# 07-POWER.net
KiCad netlist of a schematic drawn in Altium Designer
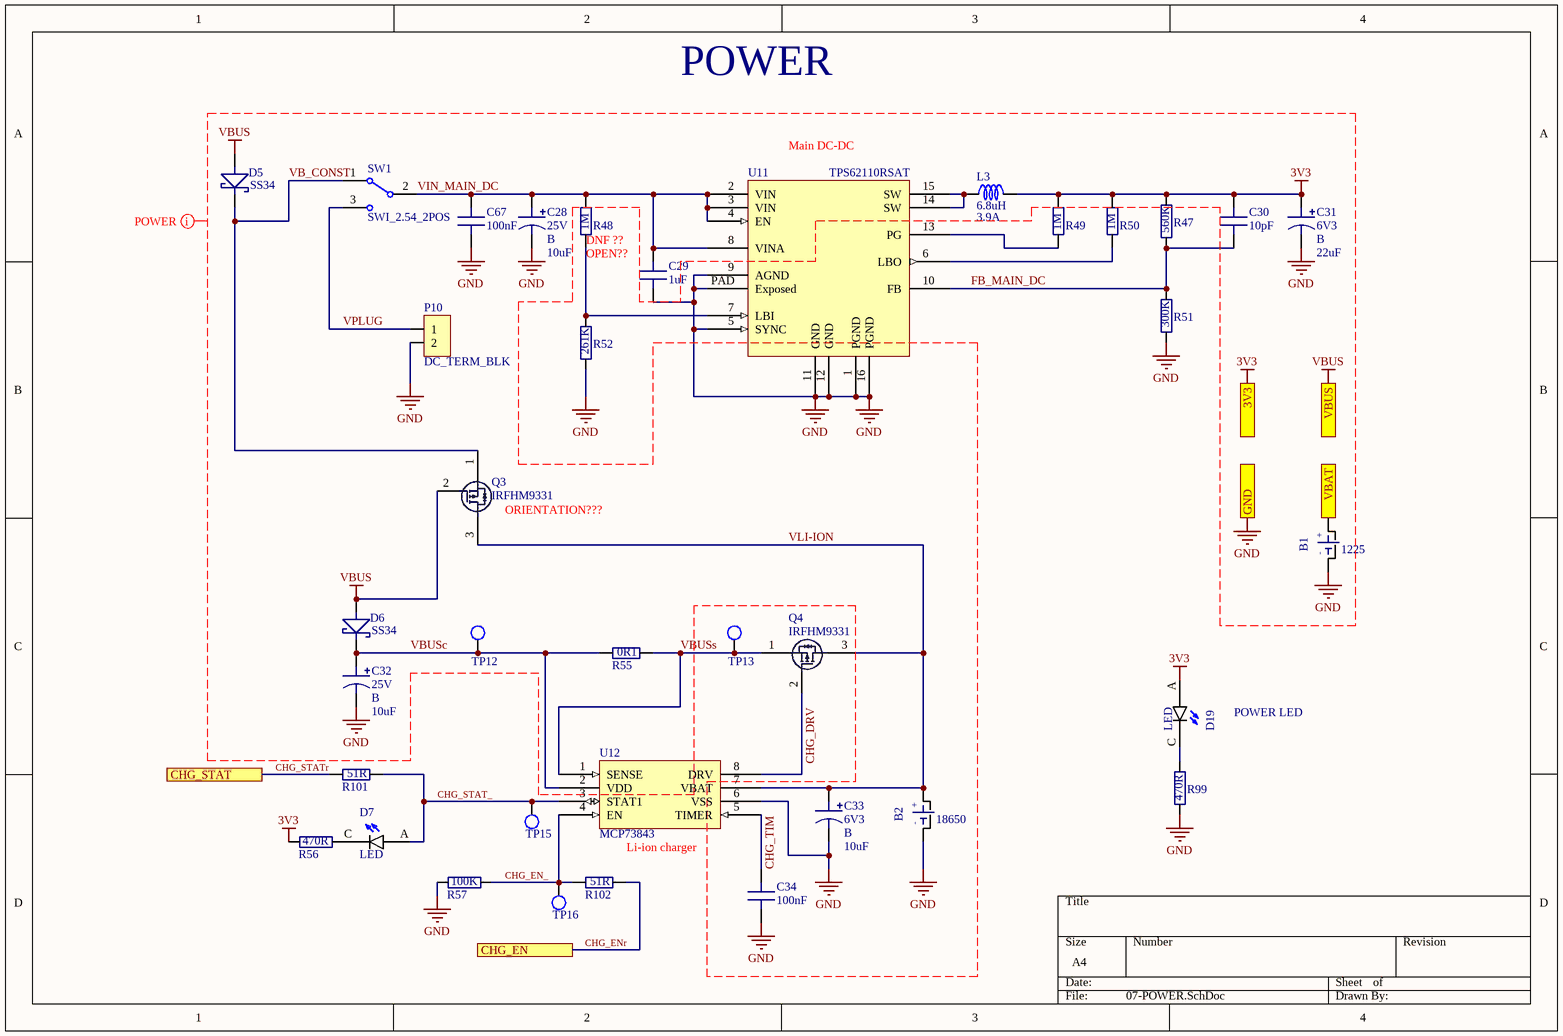
[diagram p0: 07-POWER.SchDoc]

(export (version "E")
  (design (tool "Eeschema 10.0.6"))
  (components
    (comp (ref "B1")
      (value "CR12XX_BH500")
      (footprint "BH500-CR1216/20/25-COMB")
      (description "Coin Cell Battery 3V 12 X 2.5 mm 48mA Holder")
      (fields
        (field (name "MP") "BR1225")
        (field (name "MF") "Panasonic Battery")
        (field (name "SIZE") "1225")
      )
      (libsource (lib "A.Shelestov_Batteries") (part "CR12XX_BH500"))
    )
    (comp (ref "B2")
      (value "18650_KEYS1042_HOLDER")
      (footprint "18650-COMBI")
      (description "18650 Li-ion Battery Holder")
      (fields (field (name "SIZE") "18650"))
      (libsource (lib "A.Shelestov_Batteries") (part "18650_KEYS1042_HOLDER"))
    )
    (comp (ref "C28")
      (value "10uF")
      (footprint "CAP_SIZE_B")
      (description "Tantalum capacitor")
      (fields (field (name "VOLTAGE") "25V") (field (name "SIZE") "B"))
      (libsource (lib "A.Shelestov_Capacitors") (part "CAP_B_10uF_25V"))
    )
    (comp (ref "C29")
      (value "1uF")
      (footprint "C0805")
      (description "Ceramic capacitor")
      (fields (field (name "VOLTAGE") "25V"))
      (libsource (lib "A.Shelestov_Capacitors") (part "C0805_1uF_25V"))
    )
    (comp (ref "C30")
      (value "10pF")
      (footprint "C0603")
      (description "Ceramic capacitor")
      (fields (field (name "VOLTAGE") "25V"))
      (libsource (lib "A.Shelestov_Capacitors") (part "C0603_10pF_25V"))
    )
    (comp (ref "C31")
      (value "22uF")
      (footprint "CAP_SIZE_B")
      (description "Tantalum capacitor")
      (fields (field (name "VOLTAGE") "6V3") (field (name "SIZE") "B"))
      (libsource (lib "A.Shelestov_Capacitors") (part "CAP_B_22uF_6V3"))
    )
    (comp (ref "C32")
      (value "10uF")
      (footprint "CAP_SIZE_B")
      (description "Tantalum capacitor")
      (fields (field (name "VOLTAGE") "25V") (field (name "SIZE") "B"))
      (libsource (lib "A.Shelestov_Capacitors") (part "CAP_B_10uF_25V"))
    )
    (comp (ref "C33")
      (value "10uF")
      (footprint "CAP_SIZE_B")
      (description "Tantalum capacitor")
      (fields (field (name "VOLTAGE") "6V3") (field (name "SIZE") "B"))
      (libsource (lib "A.Shelestov_Capacitors") (part "CAP_B_10uF_6V3"))
    )
    (comp (ref "C34")
      (value "100nF")
      (footprint "C0805")
      (description "Ceramic capacitor")
      (fields (field (name "VOLTAGE") "25V"))
      (libsource (lib "A.Shelestov_Capacitors") (part "C0805_100nF_25V"))
    )
    (comp (ref "C67")
      (value "100nF")
      (footprint "C0805")
      (description "Ceramic capacitor")
      (fields (field (name "VOLTAGE") "25V"))
      (libsource (lib "A.Shelestov_Capacitors") (part "C0805_100nF_25V"))
    )
    (comp (ref "D5")
      (value "SMD-DIODE-SCHOTTKY-40V-3A(DO-214AB)")
      (footprint "DO-214AC")
      (description "Rectifier, Schottky; DO-214AB; 3.0A IF; 0.75V; 40V; 100A IFRM; 10000V/us; 1000pF")
      (fields (field (name "MF") "Vishay") (field (name "MP") "SS34-E3/57T") (field (name "NAME") "SS34"))
      (libsource (lib "ComponentsLib") (part "D_SS-34"))
    )
    (comp (ref "D6")
      (value "SMD-DIODE-SCHOTTKY-40V-3A(DO-214AB)")
      (footprint "DO-214AC")
      (description "Rectifier, Schottky; DO-214AB; 3.0A IF; 0.75V; 40V; 100A IFRM; 10000V/us; 1000pF")
      (fields (field (name "MF") "Vishay") (field (name "MP") "SS34-E3/57T") (field (name "NAME") "SS34"))
      (libsource (lib "ComponentsLib") (part "D_SS-34"))
    )
    (comp (ref "D7")
      (value "LED")
      (footprint "LED_0604")
      (description "Led General")
      (fields (field (name "MF") "Dialight") (field (name "MP") "598-8140-107F"))
      (libsource (lib "ComponentsLib") (part "LED"))
    )
    (comp (ref "D19")
      (value "LED")
      (footprint "LED_0604")
      (description "Led General")
      (fields (field (name "MF") "Dialight") (field (name "MP") "598-8140-107F"))
      (libsource (lib "ComponentsLib") (part "LED"))
    )
    (comp (ref "L3")
      (value "*")
      (footprint "L_CDRH8D43")
      (description "Inductor Generic")
      (fields (field (name "CURRENT") "3.9A") (field (name "INDUCTIVITY") "6.8uH"))
      (libsource (lib "A.Shelestov_Inductors") (part "L_CDHR8D43_6.8uH_3.9A"))
    )
    (comp (ref "P10")
      (value "DC_TERM_BLK")
      (footprint "TERM_BLK_2.54")
      (libsource (lib "ComponentsLib") (part "DC_TERM_BLK"))
    )
    (comp (ref "Q3")
      (value "IRFHM9331")
      (footprint "PQFN-3x3")
      (libsource (lib "ComponentsLib") (part "IRFHM9331"))
    )
    (comp (ref "Q4")
      (value "IRFHM9331")
      (footprint "PQFN-3x3")
      (libsource (lib "ComponentsLib") (part "IRFHM9331"))
    )
    (comp (ref "R47")
      (value "~")
      (footprint "R0805")
      (description "Resistor General")
      (fields (field (name "TOLERANCE") "1%") (field (name "RESISTANCE") "560K"))
      (libsource (lib "A.Shelestov_Resistors") (part "R0805_560K_1%"))
    )
    (comp (ref "R48")
      (value "~")
      (footprint "R0805")
      (description "Resistor General")
      (fields (field (name "TOLERANCE") "1%") (field (name "RESISTANCE") "1M"))
      (libsource (lib "A.Shelestov_Resistors") (part "R0805_1M_1%"))
    )
    (comp (ref "R49")
      (value "~")
      (footprint "R0805")
      (description "Resistor General")
      (fields (field (name "TOLERANCE") "1%") (field (name "RESISTANCE") "1M"))
      (libsource (lib "A.Shelestov_Resistors") (part "R0805_1M_1%"))
    )
    (comp (ref "R50")
      (value "~")
      (footprint "R0805")
      (description "Resistor General")
      (fields (field (name "TOLERANCE") "1%") (field (name "RESISTANCE") "1M"))
      (libsource (lib "A.Shelestov_Resistors") (part "R0805_1M_1%"))
    )
    (comp (ref "R51")
      (value "~")
      (footprint "R0805")
      (description "Resistor General")
      (fields (field (name "TOLERANCE") "1%") (field (name "RESISTANCE") "300K"))
      (libsource (lib "A.Shelestov_Resistors") (part "R0805_300K_1%"))
    )
    (comp (ref "R52")
      (value "~")
      (footprint "R0805")
      (description "Resistor General")
      (fields (field (name "TOLERANCE") "1%") (field (name "RESISTANCE") "261K"))
      (libsource (lib "A.Shelestov_Resistors") (part "R0805_261K_1%"))
    )
    (comp (ref "R55")
      (value "~")
      (footprint "R2512")
      (description "Resistor General")
      (fields (field (name "RESISTANCE") "0R1"))
      (libsource (lib "A.Shelestov_Resistors") (part "R2512_0R1_1%"))
    )
    (comp (ref "R56")
      (value "~")
      (footprint "R0603")
      (description "Resistor General")
      (fields (field (name "TOLERANCE") "5%") (field (name "RESISTANCE") "470R"))
      (libsource (lib "A.Shelestov_Resistors") (part "R0603_470R"))
    )
    (comp (ref "R57")
      (value "~")
      (footprint "R0603")
      (description "Resistor General")
      (fields (field (name "TOLERANCE") "5%") (field (name "RESISTANCE") "100K"))
      (libsource (lib "A.Shelestov_Resistors") (part "R0603_100K"))
    )
    (comp (ref "R99")
      (value "~")
      (footprint "R0603")
      (description "Resistor General")
      (fields (field (name "TOLERANCE") "5%") (field (name "RESISTANCE") "470R"))
      (libsource (lib "A.Shelestov_Resistors") (part "R0603_470R"))
    )
    (comp (ref "R101")
      (value "~")
      (footprint "R0402")
      (description "Resistor General")
      (fields (field (name "RESISTANCE") "51R"))
      (libsource (lib "A.Shelestov_Resistors") (part "R0402_51R"))
    )
    (comp (ref "R102")
      (value "~")
      (footprint "R0402")
      (description "Resistor General")
      (fields (field (name "RESISTANCE") "51R"))
      (libsource (lib "A.Shelestov_Resistors") (part "R0402_51R"))
    )
    (comp (ref "SW1")
      (value "SWI_2.54_2POS")
      (footprint "SW_1x3 2.54")
      (description "Generich 2 pos switch")
      (libsource (lib "ComponentsLib") (part "SWI_2.54_2POS"))
    )
    (comp (ref "TP12")
      (value "TEST_POINT")
      (footprint "TP_1mm")
      (libsource (lib "ComponentsLib") (part "TEST_POINT"))
    )
    (comp (ref "TP13")
      (value "TEST_POINT")
      (footprint "TP_1mm")
      (libsource (lib "ComponentsLib") (part "TEST_POINT"))
    )
    (comp (ref "TP15")
      (value "TEST_POINT")
      (footprint "TP_1mm")
      (libsource (lib "ComponentsLib") (part "TEST_POINT"))
    )
    (comp (ref "TP16")
      (value "TEST_POINT")
      (footprint "TP_1mm")
      (libsource (lib "ComponentsLib") (part "TEST_POINT"))
    )
    (comp (ref "U11")
      (value "TPS62110RSAT")
      (footprint "VQFN-16")
      (description "TPS6211x 17-V, 1.5-A, Synchronous Step-Down Converter")
      (libsource (lib "ComponentsLib") (part "TPS62110RSAT"))
    )
    (comp (ref "U12")
      (value "MCP73843")
      (footprint "MSOP-8-SOP65P490X110-8N")
      (description "MCP73843 Single Li-ion cell charger IC")
      (fields (field (name "MF") "Microchip"))
      (libsource (lib "ComponentsLib") (part "MCP73843"))
    )
  )
  (nets
    (net (code "1") (name "/CHG_DRV") (class "Default")
      (node (ref "Q4") (pin "2") (pinfunction "G_2") (pintype "passive"))
      (node (ref "U12") (pin "8") (pinfunction "DRV_8") (pintype "power_in"))
    )
    (net (code "2") (name "/CHG_EN_") (class "Default")
      (node (ref "R102") (pin "1") (pinfunction "1_1") (pintype "passive"))
      (node (ref "R57") (pin "2") (pinfunction "2_2") (pintype "passive"))
      (node (ref "TP16") (pin "1") (pinfunction "1_1") (pintype "passive"))
      (node (ref "U12") (pin "4") (pinfunction "EN_4") (pintype "input"))
    )
    (net (code "3") (name "/CHG_ENr") (class "Default")
      (node (ref "R102") (pin "2") (pinfunction "2_2") (pintype "passive"))
    )
    (net (code "4") (name "/CHG_STAT_") (class "Default")
      (node (ref "D7") (pin "A") (pinfunction "A_A") (pintype "passive"))
      (node (ref "R101") (pin "2") (pinfunction "2_2") (pintype "passive"))
      (node (ref "TP15") (pin "1") (pinfunction "1_1") (pintype "passive"))
      (node (ref "U12") (pin "3") (pinfunction "STAT1_3") (pintype "bidirectional"))
    )
    (net (code "5") (name "/CHG_STATr") (class "Default")
      (node (ref "R101") (pin "1") (pinfunction "1_1") (pintype "passive"))
    )
    (net (code "6") (name "/CHG_TIM") (class "Default")
      (node (ref "C34") (pin "2") (pinfunction "2_2") (pintype "passive"))
      (node (ref "U12") (pin "5") (pinfunction "TIMER_5") (pintype "input"))
    )
    (net (code "7") (name "/FB_MAIN_DC") (class "Default")
      (node (ref "C30") (pin "2") (pinfunction "2_2") (pintype "passive"))
      (node (ref "R47") (pin "1") (pinfunction "1_1") (pintype "passive"))
      (node (ref "R51") (pin "2") (pinfunction "2_2") (pintype "passive"))
      (node (ref "U11") (pin "10") (pinfunction "FB_10") (pintype "power_in"))
    )
    (net (code "8") (name "/VBAT") (class "Default")
      (node (ref "B1") (pin "POS") (pinfunction "POS_POS") (pintype "passive"))
    )
    (net (code "9") (name "/VBUSc") (class "Default")
      (node (ref "C32") (pin "1") (pinfunction "1_1") (pintype "passive"))
      (node (ref "D6") (pin "C") (pinfunction "NEG_C") (pintype "passive"))
      (node (ref "R55") (pin "1") (pinfunction "1_1") (pintype "passive"))
      (node (ref "TP12") (pin "1") (pinfunction "1_1") (pintype "passive"))
      (node (ref "U12") (pin "2") (pinfunction "VDD_2") (pintype "power_in"))
    )
    (net (code "10") (name "/VBUSs") (class "Default")
      (node (ref "Q4") (pin "1") (pinfunction "S_1") (pintype "passive"))
      (node (ref "R55") (pin "2") (pinfunction "2_2") (pintype "passive"))
      (node (ref "TP13") (pin "1") (pinfunction "1_1") (pintype "passive"))
      (node (ref "U12") (pin "1") (pinfunction "SENSE_1") (pintype "input"))
    )
    (net (code "11") (name "/VB_CONST") (class "Default")
      (node (ref "D5") (pin "C") (pinfunction "NEG_C") (pintype "passive"))
      (node (ref "Q3") (pin "1") (pinfunction "S_1") (pintype "passive"))
      (node (ref "SW1") (pin "1") (pinfunction "1_1") (pintype "passive"))
    )
    (net (code "12") (name "/VIN_MAIN_DC") (class "Default")
      (node (ref "C28") (pin "1") (pinfunction "1_1") (pintype "passive"))
      (node (ref "C29") (pin "2") (pinfunction "2_2") (pintype "passive"))
      (node (ref "C67") (pin "2") (pinfunction "2_2") (pintype "passive"))
      (node (ref "R48") (pin "2") (pinfunction "2_2") (pintype "passive"))
      (node (ref "SW1") (pin "2") (pinfunction "2_2") (pintype "passive"))
      (node (ref "U11") (pin "2") (pinfunction "VIN_2") (pintype "power_in"))
      (node (ref "U11") (pin "3") (pinfunction "VIN_3") (pintype "power_in"))
      (node (ref "U11") (pin "4") (pinfunction "EN_4") (pintype "input"))
      (node (ref "U11") (pin "8") (pinfunction "VINA_8") (pintype "power_in"))
    )
    (net (code "13") (name "/VLI-ION") (class "Default")
      (node (ref "B2") (pin "POS") (pinfunction "POS_POS") (pintype "passive"))
      (node (ref "C33") (pin "1") (pinfunction "1_1") (pintype "passive"))
      (node (ref "Q3") (pin "3") (pinfunction "D_3") (pintype "passive"))
      (node (ref "Q4") (pin "3") (pinfunction "D_3") (pintype "passive"))
      (node (ref "U12") (pin "7") (pinfunction "VBAT_7") (pintype "power_in"))
    )
    (net (code "14") (name "/VPLUG") (class "Default")
      (node (ref "P10") (pin "1") (pinfunction "1_1") (pintype "passive"))
      (node (ref "SW1") (pin "3") (pinfunction "3_3") (pintype "passive"))
    )
    (net (code "15") (name "3V3") (class "Default")
      (node (ref "C30") (pin "1") (pinfunction "1_1") (pintype "passive"))
      (node (ref "C31") (pin "1") (pinfunction "1_1") (pintype "passive"))
      (node (ref "D19") (pin "A") (pinfunction "A_A") (pintype "passive"))
      (node (ref "L3") (pin "2") (pinfunction "2_2") (pintype "passive"))
      (node (ref "R47") (pin "2") (pinfunction "2_2") (pintype "passive"))
      (node (ref "R49") (pin "2") (pinfunction "2_2") (pintype "passive"))
      (node (ref "R50") (pin "2") (pinfunction "2_2") (pintype "passive"))
      (node (ref "R56") (pin "1") (pinfunction "1_1") (pintype "passive"))
    )
    (net (code "16") (name "GND") (class "Default")
      (node (ref "B1") (pin "NEG") (pinfunction "NEG_NEG") (pintype "passive"))
      (node (ref "B2") (pin "NEG") (pinfunction "NEG_NEG") (pintype "passive"))
      (node (ref "C28") (pin "2") (pinfunction "2_2") (pintype "passive"))
      (node (ref "C29") (pin "1") (pinfunction "1_1") (pintype "passive"))
      (node (ref "C31") (pin "2") (pinfunction "2_2") (pintype "passive"))
      (node (ref "C32") (pin "2") (pinfunction "2_2") (pintype "passive"))
      (node (ref "C33") (pin "2") (pinfunction "2_2") (pintype "passive"))
      (node (ref "C34") (pin "1") (pinfunction "1_1") (pintype "passive"))
      (node (ref "C67") (pin "1") (pinfunction "1_1") (pintype "passive"))
      (node (ref "P10") (pin "2") (pinfunction "2_2") (pintype "passive"))
      (node (ref "R51") (pin "1") (pinfunction "1_1") (pintype "passive"))
      (node (ref "R52") (pin "1") (pinfunction "1_1") (pintype "passive"))
      (node (ref "R57") (pin "1") (pinfunction "1_1") (pintype "passive"))
      (node (ref "R99") (pin "1") (pinfunction "1_1") (pintype "passive"))
      (node (ref "U11") (pin "1") (pinfunction "PGND_1") (pintype "power_in"))
      (node (ref "U11") (pin "11") (pinfunction "GND_11") (pintype "power_in"))
      (node (ref "U11") (pin "12") (pinfunction "GND_12") (pintype "power_in"))
      (node (ref "U11") (pin "16") (pinfunction "PGND_16") (pintype "power_in"))
      (node (ref "U11") (pin "5") (pinfunction "SYNC_5") (pintype "input"))
      (node (ref "U11") (pin "9") (pinfunction "AGND_9") (pintype "power_in"))
      (node (ref "U11") (pin "PAD") (pinfunction "Exposed_PAD") (pintype "power_in"))
      (node (ref "U12") (pin "6") (pinfunction "VSS_6") (pintype "power_in"))
    )
    (net (code "17") (name "Net-(D7-PadC)") (class "Default")
      (node (ref "D7") (pin "C") (pinfunction "C_C") (pintype "passive"))
      (node (ref "R56") (pin "2") (pinfunction "2_2") (pintype "passive"))
    )
    (net (code "18") (name "Net-(D19-PadC)") (class "Default")
      (node (ref "D19") (pin "C") (pinfunction "C_C") (pintype "passive"))
      (node (ref "R99") (pin "2") (pinfunction "2_2") (pintype "passive"))
    )
    (net (code "19") (name "Net-(L3-Pad1)") (class "Default")
      (node (ref "L3") (pin "1") (pinfunction "1_1") (pintype "passive"))
      (node (ref "U11") (pin "14") (pinfunction "SW_14") (pintype "power_in"))
      (node (ref "U11") (pin "15") (pinfunction "SW_15") (pintype "power_in"))
    )
    (net (code "20") (name "Net-(U11-LBI)") (class "Default")
      (node (ref "R48") (pin "1") (pinfunction "1_1") (pintype "passive"))
      (node (ref "R52") (pin "2") (pinfunction "2_2") (pintype "passive"))
      (node (ref "U11") (pin "7") (pinfunction "LBI_7") (pintype "input"))
    )
    (net (code "21") (name "Net-(U11-LBO)") (class "Default")
      (node (ref "R50") (pin "1") (pinfunction "1_1") (pintype "passive"))
      (node (ref "U11") (pin "6") (pinfunction "LBO_6") (pintype "output"))
    )
    (net (code "22") (name "Net-(U11-PG)") (class "Default")
      (node (ref "R49") (pin "1") (pinfunction "1_1") (pintype "passive"))
      (node (ref "U11") (pin "13") (pinfunction "PG_13") (pintype "power_in"))
    )
    (net (code "23") (name "VBUS") (class "Default")
      (node (ref "D5") (pin "A") (pinfunction "POS_A") (pintype "passive"))
      (node (ref "D6") (pin "A") (pinfunction "POS_A") (pintype "passive"))
      (node (ref "Q3") (pin "2") (pinfunction "G_2") (pintype "passive"))
    )
  )
)
